# Transmissor_nano.net
KiCad netlist of a schematic drawn in EAGLE
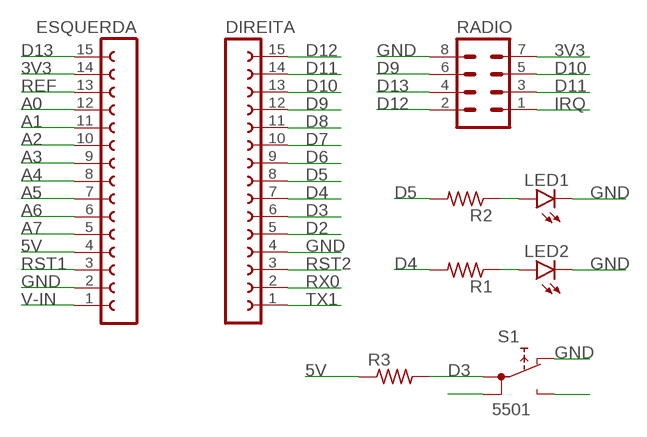
[diagram p0: schematic, sheet 1]

(export (version "E")
  (design (tool "Eeschema 10.0.6"))
  (components
    (comp (ref "DIREITA")
      (value "FE15-1")
      (footprint "eagle-import:FE15")
      (libsource (lib "eagle-import") (part "FE15-1"))
    )
    (comp (ref "ESQUERDA")
      (value "FE15-1")
      (footprint "eagle-import:FE15")
      (libsource (lib "eagle-import") (part "FE15-1"))
    )
    (comp (ref "LED1")
      (value "LED5MM")
      (footprint "eagle-import:LED5MM")
      (libsource (lib "eagle-import") (part "LED5MM"))
    )
    (comp (ref "LED2")
      (value "LED5MM")
      (footprint "eagle-import:LED5MM")
      (libsource (lib "eagle-import") (part "LED5MM"))
    )
    (comp (ref "R1")
      (value "R-US_0204/7")
      (footprint "eagle-import:0204_7")
      (libsource (lib "eagle-import") (part "R-US_0204/7"))
    )
    (comp (ref "R2")
      (value "R-US_0204/7")
      (footprint "eagle-import:0204_7")
      (libsource (lib "eagle-import") (part "R-US_0204/7"))
    )
    (comp (ref "R3")
      (value "R-US_0204/7")
      (footprint "eagle-import:0204_7")
      (libsource (lib "eagle-import") (part "R-US_0204/7"))
    )
    (comp (ref "RADIO")
      (value "MA04-2")
      (footprint "eagle-import:MA04-2")
      (libsource (lib "eagle-import") (part "MA04-2"))
    )
    (comp (ref "S1")
      (value "5501")
      (footprint "eagle-import:5501")
      (libsource (lib "eagle-import") (part "55?01"))
    )
  )
  (nets
    (net (code "1") (name "/3V3") (class "Default")
      (node (ref "ESQUERDA") (pin "14") (pinfunction "14_14") (pintype "passive"))
      (node (ref "RADIO") (pin "7") (pinfunction "7_7") (pintype "passive"))
    )
    (net (code "2") (name "/5V") (class "Default")
      (node (ref "ESQUERDA") (pin "4") (pinfunction "4_4") (pintype "passive"))
      (node (ref "R3") (pin "1") (pinfunction "1_1") (pintype "passive"))
    )
    (net (code "3") (name "/A0") (class "Default")
      (node (ref "ESQUERDA") (pin "12") (pinfunction "12_12") (pintype "passive"))
    )
    (net (code "4") (name "/A1") (class "Default")
      (node (ref "ESQUERDA") (pin "11") (pinfunction "11_11") (pintype "passive"))
    )
    (net (code "5") (name "/A2") (class "Default")
      (node (ref "ESQUERDA") (pin "10") (pinfunction "10_10") (pintype "passive"))
    )
    (net (code "6") (name "/A3") (class "Default")
      (node (ref "ESQUERDA") (pin "9") (pinfunction "9_9") (pintype "passive"))
    )
    (net (code "7") (name "/A4") (class "Default")
      (node (ref "ESQUERDA") (pin "8") (pinfunction "8_8") (pintype "passive"))
    )
    (net (code "8") (name "/A5") (class "Default")
      (node (ref "ESQUERDA") (pin "7") (pinfunction "7_7") (pintype "passive"))
    )
    (net (code "9") (name "/A6") (class "Default")
      (node (ref "ESQUERDA") (pin "6") (pinfunction "6_6") (pintype "passive"))
    )
    (net (code "10") (name "/A7") (class "Default")
      (node (ref "ESQUERDA") (pin "5") (pinfunction "5_5") (pintype "passive"))
    )
    (net (code "11") (name "/D2") (class "Default")
      (node (ref "DIREITA") (pin "5") (pinfunction "5_5") (pintype "passive"))
    )
    (net (code "12") (name "/D3") (class "Default")
      (node (ref "DIREITA") (pin "6") (pinfunction "6_6") (pintype "passive"))
      (node (ref "R3") (pin "2") (pinfunction "2_2") (pintype "passive"))
      (node (ref "S1") (pin "1A") (pinfunction "1A_1A") (pintype "passive"))
    )
    (net (code "13") (name "/D4") (class "Default")
      (node (ref "DIREITA") (pin "7") (pinfunction "7_7") (pintype "passive"))
      (node (ref "R1") (pin "2") (pinfunction "2_2") (pintype "passive"))
    )
    (net (code "14") (name "/D5") (class "Default")
      (node (ref "DIREITA") (pin "8") (pinfunction "8_8") (pintype "passive"))
      (node (ref "R2") (pin "2") (pinfunction "2_2") (pintype "passive"))
    )
    (net (code "15") (name "/D6") (class "Default")
      (node (ref "DIREITA") (pin "9") (pinfunction "9_9") (pintype "passive"))
    )
    (net (code "16") (name "/D7") (class "Default")
      (node (ref "DIREITA") (pin "10") (pinfunction "10_10") (pintype "passive"))
    )
    (net (code "17") (name "/D8") (class "Default")
      (node (ref "DIREITA") (pin "11") (pinfunction "11_11") (pintype "passive"))
    )
    (net (code "18") (name "/D9") (class "Default")
      (node (ref "DIREITA") (pin "12") (pinfunction "12_12") (pintype "passive"))
      (node (ref "RADIO") (pin "6") (pinfunction "6_6") (pintype "passive"))
    )
    (net (code "19") (name "/D10") (class "Default")
      (node (ref "DIREITA") (pin "13") (pinfunction "13_13") (pintype "passive"))
      (node (ref "RADIO") (pin "5") (pinfunction "5_5") (pintype "passive"))
    )
    (net (code "20") (name "/D11") (class "Default")
      (node (ref "DIREITA") (pin "14") (pinfunction "14_14") (pintype "passive"))
      (node (ref "RADIO") (pin "3") (pinfunction "3_3") (pintype "passive"))
    )
    (net (code "21") (name "/D12") (class "Default")
      (node (ref "DIREITA") (pin "15") (pinfunction "15_15") (pintype "passive"))
      (node (ref "RADIO") (pin "2") (pinfunction "2_2") (pintype "passive"))
    )
    (net (code "22") (name "/D13") (class "Default")
      (node (ref "ESQUERDA") (pin "15") (pinfunction "15_15") (pintype "passive"))
      (node (ref "RADIO") (pin "4") (pinfunction "4_4") (pintype "passive"))
    )
    (net (code "23") (name "/GND") (class "Default")
      (node (ref "DIREITA") (pin "4") (pinfunction "4_4") (pintype "passive"))
      (node (ref "ESQUERDA") (pin "2") (pinfunction "2_2") (pintype "passive"))
      (node (ref "LED1") (pin "K") (pinfunction "C_K") (pintype "passive"))
      (node (ref "LED2") (pin "K") (pinfunction "C_K") (pintype "passive"))
      (node (ref "RADIO") (pin "8") (pinfunction "8_8") (pintype "passive"))
      (node (ref "S1") (pin "NC") (pinfunction "NC_NC") (pintype "passive"))
    )
    (net (code "24") (name "/IRQ") (class "Default")
      (node (ref "RADIO") (pin "1") (pinfunction "1_1") (pintype "passive"))
    )
    (net (code "25") (name "/REF") (class "Default")
      (node (ref "ESQUERDA") (pin "13") (pinfunction "13_13") (pintype "passive"))
    )
    (net (code "26") (name "/RST1") (class "Default")
      (node (ref "ESQUERDA") (pin "3") (pinfunction "3_3") (pintype "passive"))
    )
    (net (code "27") (name "/RST2") (class "Default")
      (node (ref "DIREITA") (pin "3") (pinfunction "3_3") (pintype "passive"))
    )
    (net (code "28") (name "/RX0") (class "Default")
      (node (ref "DIREITA") (pin "2") (pinfunction "2_2") (pintype "passive"))
    )
    (net (code "29") (name "/TX1") (class "Default")
      (node (ref "DIREITA") (pin "1") (pinfunction "1_1") (pintype "passive"))
    )
    (net (code "30") (name "/V-IN") (class "Default")
      (node (ref "ESQUERDA") (pin "1") (pinfunction "1_1") (pintype "passive"))
    )
    (net (code "31") (name "Net-(LED1-PadA)") (class "Default")
      (node (ref "LED1") (pin "A") (pinfunction "A_A") (pintype "passive"))
      (node (ref "R2") (pin "1") (pinfunction "1_1") (pintype "passive"))
    )
    (net (code "32") (name "Net-(LED2-PadA)") (class "Default")
      (node (ref "LED2") (pin "A") (pinfunction "A_A") (pintype "passive"))
      (node (ref "R1") (pin "1") (pinfunction "1_1") (pintype "passive"))
    )
    (net (code "33") (name "unconnected-(S1-Pad1B)") (class "Default")
      (node (ref "S1") (pin "1B") (pinfunction "1B_1B") (pintype "passive"))
    )
    (net (code "34") (name "unconnected-(S1-PadNO)") (class "Default")
      (node (ref "S1") (pin "NO") (pinfunction "NO_NO") (pintype "passive"))
    )
  )
)
